# untitled.net
KiCad netlist of a schematic drawn in EAGLE
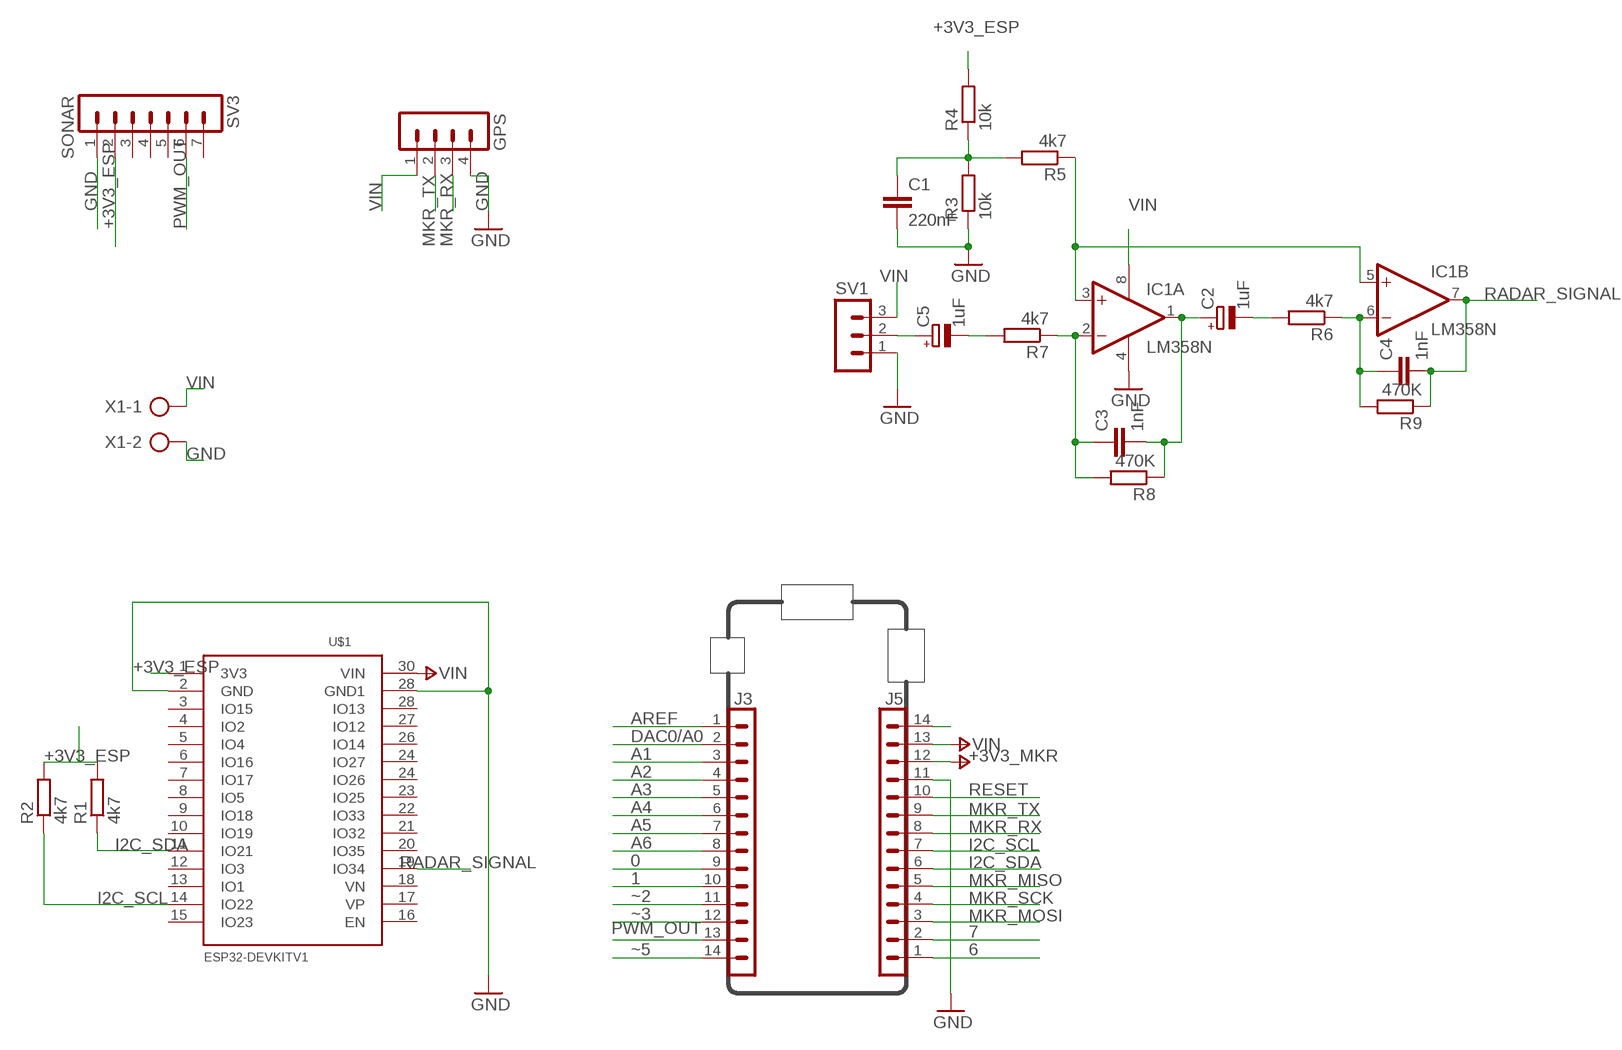
[diagram p0: schematic, sheet 1]

(export (version "E")
  (design (tool "Eeschema 10.0.6"))
  (components
    (comp (ref "C1")
      (value "220nF")
      (footprint "eagle-import:C025-025X050")
      (libsource (lib "eagle-import") (part "C-EU025-025X050"))
    )
    (comp (ref "C2")
      (value "1uF")
      (footprint "eagle-import:E2-4")
      (libsource (lib "eagle-import") (part "CPOL-EUE2-4"))
    )
    (comp (ref "C3")
      (value "1nF")
      (footprint "eagle-import:C025-025X050")
      (libsource (lib "eagle-import") (part "C-EU025-025X050"))
    )
    (comp (ref "C4")
      (value "1nF")
      (footprint "eagle-import:C025-025X050")
      (libsource (lib "eagle-import") (part "C-EU025-025X050"))
    )
    (comp (ref "C5")
      (value "1uF")
      (footprint "eagle-import:E2-4")
      (libsource (lib "eagle-import") (part "CPOL-EUE2-4"))
    )
    (comp (ref "GPS")
      (value "MA04-1")
      (footprint "eagle-import:MA04-1")
      (libsource (lib "eagle-import") (part "MA04-1"))
    )
    (comp (ref "IC1")
      (value "LM358N")
      (footprint "eagle-import:DIL08")
      (libsource (lib "eagle-import") (part "LM358N"))
    )
    (comp (ref "J3")
      (value "-")
      (footprint "eagle-import:1X14_SMD_TH")
      (fields (field (name "MANUFACTURER") "ELDECO"))
      (libsource (lib "eagle-import") (part "PINHD-1X14-SMTH-SMD-MALE/FEMALE"))
    )
    (comp (ref "J5")
      (value "-")
      (footprint "eagle-import:1X14_SMD_TH")
      (fields (field (name "MANUFACTURER") "ELDECO"))
      (libsource (lib "eagle-import") (part "PINHD-1X14-SMTH-SMD-MALE/FEMALE"))
    )
    (comp (ref "R1")
      (value "4k7")
      (footprint "eagle-import:0207_10")
      (libsource (lib "eagle-import") (part "R-EU_0207/10"))
    )
    (comp (ref "R2")
      (value "4k7")
      (footprint "eagle-import:0207_10")
      (libsource (lib "eagle-import") (part "R-EU_0207/10"))
    )
    (comp (ref "R3")
      (value "10k")
      (footprint "eagle-import:0207_10")
      (libsource (lib "eagle-import") (part "R-EU_0207/10"))
    )
    (comp (ref "R4")
      (value "10k")
      (footprint "eagle-import:0207_10")
      (libsource (lib "eagle-import") (part "R-EU_0207/10"))
    )
    (comp (ref "R5")
      (value "4k7")
      (footprint "eagle-import:0207_10")
      (libsource (lib "eagle-import") (part "R-EU_0207/10"))
    )
    (comp (ref "R6")
      (value "4k7")
      (footprint "eagle-import:0207_10")
      (libsource (lib "eagle-import") (part "R-EU_0207/10"))
    )
    (comp (ref "R7")
      (value "4k7")
      (footprint "eagle-import:0207_10")
      (libsource (lib "eagle-import") (part "R-EU_0207/10"))
    )
    (comp (ref "R8")
      (value "470K")
      (footprint "eagle-import:0207_2V")
      (libsource (lib "eagle-import") (part "R-EU_0207/2V"))
    )
    (comp (ref "R9")
      (value "470K")
      (footprint "eagle-import:0207_2V")
      (libsource (lib "eagle-import") (part "R-EU_0207/2V"))
    )
    (comp (ref "SV1")
      (value "MA03-1")
      (footprint "eagle-import:MA03-1")
      (libsource (lib "eagle-import") (part "MA03-1"))
    )
    (comp (ref "SV3")
      (value "SONAR")
      (footprint "eagle-import:MA07-1")
      (libsource (lib "eagle-import") (part "MA07-1"))
    )
    (comp (ref "U$1")
      (value "ESP32DEVKITV1")
      (footprint "eagle-import:ESP32-DEVKITV1")
      (libsource (lib "eagle-import") (part "ESP32DEVKITV1"))
    )
    (comp (ref "X1")
      (value "AK500/2-H")
      (footprint "eagle-import:AK500_2-H")
      (libsource (lib "eagle-import") (part "AK500/2-H"))
    )
  )
  (nets
    (net (code "1") (name "+3V3") (class "Default")
      (node (ref "J5") (pin "12") (pinfunction "12_12") (pintype "passive"))
    )
    (net (code "2") (name "/+3V3_ESP") (class "Default")
      (node (ref "R1") (pin "2") (pinfunction "2_2") (pintype "passive"))
      (node (ref "R2") (pin "2") (pinfunction "2_2") (pintype "passive"))
      (node (ref "R4") (pin "2") (pinfunction "2_2") (pintype "passive"))
      (node (ref "SV3") (pin "2") (pinfunction "2_2") (pintype "passive"))
      (node (ref "U$1") (pin "1") (pinfunction "3V3_1") (pintype "bidirectional"))
    )
    (net (code "3") (name "/I2C_SCL") (class "Default")
      (node (ref "J5") (pin "7") (pinfunction "7_7") (pintype "passive"))
      (node (ref "R2") (pin "1") (pinfunction "1_1") (pintype "passive"))
      (node (ref "U$1") (pin "14") (pinfunction "IO22_14") (pintype "bidirectional"))
    )
    (net (code "4") (name "/I2C_SDA") (class "Default")
      (node (ref "J5") (pin "6") (pinfunction "6_6") (pintype "passive"))
      (node (ref "R1") (pin "1") (pinfunction "1_1") (pintype "passive"))
      (node (ref "U$1") (pin "11") (pinfunction "IO21_11") (pintype "bidirectional"))
    )
    (net (code "5") (name "/MKR_MISO") (class "Default")
      (node (ref "J5") (pin "5") (pinfunction "5_5") (pintype "passive"))
    )
    (net (code "6") (name "/MKR_MOSI") (class "Default")
      (node (ref "J5") (pin "3") (pinfunction "3_3") (pintype "passive"))
    )
    (net (code "7") (name "/MKR_RX") (class "Default")
      (node (ref "GPS") (pin "3") (pinfunction "3_3") (pintype "passive"))
      (node (ref "J5") (pin "8") (pinfunction "8_8") (pintype "passive"))
    )
    (net (code "8") (name "/MKR_SCK") (class "Default")
      (node (ref "J5") (pin "4") (pinfunction "4_4") (pintype "passive"))
    )
    (net (code "9") (name "/MKR_TX") (class "Default")
      (node (ref "GPS") (pin "2") (pinfunction "2_2") (pintype "passive"))
      (node (ref "J5") (pin "9") (pinfunction "9_9") (pintype "passive"))
    )
    (net (code "10") (name "/PWM_OUT") (class "Default")
      (node (ref "J3") (pin "13") (pinfunction "13_13") (pintype "passive"))
      (node (ref "SV3") (pin "6") (pinfunction "6_6") (pintype "passive"))
    )
    (net (code "11") (name "/RADAR_SIGNAL") (class "Default")
      (node (ref "C4") (pin "2") (pinfunction "2_2") (pintype "passive"))
      (node (ref "IC1") (pin "7") (pinfunction "OUT_7") (pintype "output"))
      (node (ref "R9") (pin "1") (pinfunction "1_1") (pintype "passive"))
      (node (ref "U$1") (pin "19") (pinfunction "IO34_19") (pintype "bidirectional"))
    )
    (net (code "12") (name "GND") (class "Default")
      (node (ref "C1") (pin "2") (pinfunction "2_2") (pintype "passive"))
      (node (ref "GPS") (pin "4") (pinfunction "4_4") (pintype "passive"))
      (node (ref "IC1") (pin "4") (pinfunction "V-_4") (pintype "power_in"))
      (node (ref "J5") (pin "11") (pinfunction "11_11") (pintype "passive"))
      (node (ref "R3") (pin "1") (pinfunction "1_1") (pintype "passive"))
      (node (ref "SV1") (pin "1") (pinfunction "1_1") (pintype "passive"))
      (node (ref "SV3") (pin "1") (pinfunction "1_1") (pintype "passive"))
      (node (ref "U$1") (pin "2") (pinfunction "GND_2") (pintype "bidirectional"))
      (node (ref "U$1") (pin "28") (pinfunction "GND1_28") (pintype "bidirectional"))
      (node (ref "X1") (pin "2") (pinfunction "KL_2") (pintype "passive"))
    )
    (net (code "13") (name "Net-(C1-Pad1)") (class "Default")
      (node (ref "C1") (pin "1") (pinfunction "1_1") (pintype "passive"))
      (node (ref "R3") (pin "2") (pinfunction "2_2") (pintype "passive"))
      (node (ref "R4") (pin "1") (pinfunction "1_1") (pintype "passive"))
      (node (ref "R5") (pin "2") (pinfunction "2_2") (pintype "passive"))
    )
    (net (code "14") (name "Net-(C2-Pad-)") (class "Default")
      (node (ref "C2") (pin "-") (pinfunction "-_-") (pintype "passive"))
      (node (ref "R6") (pin "2") (pinfunction "2_2") (pintype "passive"))
    )
    (net (code "15") (name "Net-(C5-Pad+)") (class "Default")
      (node (ref "C5") (pin "+") (pinfunction "+_+") (pintype "passive"))
      (node (ref "SV1") (pin "2") (pinfunction "2_2") (pintype "passive"))
    )
    (net (code "16") (name "Net-(C5-Pad-)") (class "Default")
      (node (ref "C5") (pin "-") (pinfunction "-_-") (pintype "passive"))
      (node (ref "R7") (pin "2") (pinfunction "2_2") (pintype "passive"))
    )
    (net (code "17") (name "Net-(IC1A-+IN)") (class "Default")
      (node (ref "IC1") (pin "3") (pinfunction "+IN_3") (pintype "input"))
      (node (ref "IC1") (pin "5") (pinfunction "+IN_5") (pintype "input"))
      (node (ref "R5") (pin "1") (pinfunction "1_1") (pintype "passive"))
    )
    (net (code "18") (name "Net-(IC1A--IN)") (class "Default")
      (node (ref "C3") (pin "1") (pinfunction "1_1") (pintype "passive"))
      (node (ref "IC1") (pin "2") (pinfunction "-IN_2") (pintype "input"))
      (node (ref "R7") (pin "1") (pinfunction "1_1") (pintype "passive"))
      (node (ref "R8") (pin "2") (pinfunction "2_2") (pintype "passive"))
    )
    (net (code "19") (name "Net-(IC1A-OUT)") (class "Default")
      (node (ref "C2") (pin "+") (pinfunction "+_+") (pintype "passive"))
      (node (ref "C3") (pin "2") (pinfunction "2_2") (pintype "passive"))
      (node (ref "IC1") (pin "1") (pinfunction "OUT_1") (pintype "output"))
      (node (ref "R8") (pin "1") (pinfunction "1_1") (pintype "passive"))
    )
    (net (code "20") (name "Net-(IC1B--IN)") (class "Default")
      (node (ref "C4") (pin "1") (pinfunction "1_1") (pintype "passive"))
      (node (ref "IC1") (pin "6") (pinfunction "-IN_6") (pintype "input"))
      (node (ref "R6") (pin "1") (pinfunction "1_1") (pintype "passive"))
      (node (ref "R9") (pin "2") (pinfunction "2_2") (pintype "passive"))
    )
    (net (code "21") (name "VIN") (class "Default")
      (node (ref "GPS") (pin "1") (pinfunction "1_1") (pintype "passive"))
      (node (ref "IC1") (pin "8") (pinfunction "V+_8") (pintype "power_in"))
      (node (ref "J5") (pin "13") (pinfunction "13_13") (pintype "passive"))
      (node (ref "SV1") (pin "3") (pinfunction "3_3") (pintype "passive"))
      (node (ref "U$1") (pin "30") (pinfunction "VIN_30") (pintype "bidirectional"))
      (node (ref "X1") (pin "1") (pinfunction "KL_1") (pintype "passive"))
    )
    (net (code "22") (name "unconnected-(J3-Pad1)") (class "Default")
      (node (ref "J3") (pin "1") (pinfunction "1_1") (pintype "passive"))
    )
    (net (code "23") (name "unconnected-(J3-Pad2)") (class "Default")
      (node (ref "J3") (pin "2") (pinfunction "2_2") (pintype "passive"))
    )
    (net (code "24") (name "unconnected-(J3-Pad3)") (class "Default")
      (node (ref "J3") (pin "3") (pinfunction "3_3") (pintype "passive"))
    )
    (net (code "25") (name "unconnected-(J3-Pad4)") (class "Default")
      (node (ref "J3") (pin "4") (pinfunction "4_4") (pintype "passive"))
    )
    (net (code "26") (name "unconnected-(J3-Pad5)") (class "Default")
      (node (ref "J3") (pin "5") (pinfunction "5_5") (pintype "passive"))
    )
    (net (code "27") (name "unconnected-(J3-Pad6)") (class "Default")
      (node (ref "J3") (pin "6") (pinfunction "6_6") (pintype "passive"))
    )
    (net (code "28") (name "unconnected-(J3-Pad7)") (class "Default")
      (node (ref "J3") (pin "7") (pinfunction "7_7") (pintype "passive"))
    )
    (net (code "29") (name "unconnected-(J3-Pad8)") (class "Default")
      (node (ref "J3") (pin "8") (pinfunction "8_8") (pintype "passive"))
    )
    (net (code "30") (name "unconnected-(J3-Pad9)") (class "Default")
      (node (ref "J3") (pin "9") (pinfunction "9_9") (pintype "passive"))
    )
    (net (code "31") (name "unconnected-(J3-Pad10)") (class "Default")
      (node (ref "J3") (pin "10") (pinfunction "10_10") (pintype "passive"))
    )
    (net (code "32") (name "unconnected-(J3-Pad11)") (class "Default")
      (node (ref "J3") (pin "11") (pinfunction "11_11") (pintype "passive"))
    )
    (net (code "33") (name "unconnected-(J3-Pad12)") (class "Default")
      (node (ref "J3") (pin "12") (pinfunction "12_12") (pintype "passive"))
    )
    (net (code "34") (name "unconnected-(J3-Pad14)") (class "Default")
      (node (ref "J3") (pin "14") (pinfunction "14_14") (pintype "passive"))
    )
    (net (code "35") (name "unconnected-(J5-Pad1)") (class "Default")
      (node (ref "J5") (pin "1") (pinfunction "1_1") (pintype "passive"))
    )
    (net (code "36") (name "unconnected-(J5-Pad2)") (class "Default")
      (node (ref "J5") (pin "2") (pinfunction "2_2") (pintype "passive"))
    )
    (net (code "37") (name "unconnected-(J5-Pad10)") (class "Default")
      (node (ref "J5") (pin "10") (pinfunction "10_10") (pintype "passive"))
    )
    (net (code "38") (name "unconnected-(J5-Pad14)") (class "Default")
      (node (ref "J5") (pin "14") (pinfunction "14_14") (pintype "passive"))
    )
    (net (code "39") (name "unconnected-(SV3-Pad3)") (class "Default")
      (node (ref "SV3") (pin "3") (pinfunction "3_3") (pintype "passive"))
    )
    (net (code "40") (name "unconnected-(SV3-Pad4)") (class "Default")
      (node (ref "SV3") (pin "4") (pinfunction "4_4") (pintype "passive"))
    )
    (net (code "41") (name "unconnected-(SV3-Pad5)") (class "Default")
      (node (ref "SV3") (pin "5") (pinfunction "5_5") (pintype "passive"))
    )
    (net (code "42") (name "unconnected-(SV3-Pad7)") (class "Default")
      (node (ref "SV3") (pin "7") (pinfunction "7_7") (pintype "passive"))
    )
    (net (code "43") (name "unconnected-(U$1-EN-Pad16)") (class "Default")
      (node (ref "U$1") (pin "16") (pinfunction "EN_16") (pintype "bidirectional"))
    )
    (net (code "44") (name "unconnected-(U$1-IO1-Pad13)") (class "Default")
      (node (ref "U$1") (pin "13") (pinfunction "IO1_13") (pintype "bidirectional"))
    )
    (net (code "45") (name "unconnected-(U$1-IO2-Pad4)") (class "Default")
      (node (ref "U$1") (pin "4") (pinfunction "IO2_4") (pintype "bidirectional"))
    )
    (net (code "46") (name "unconnected-(U$1-IO3-Pad12)") (class "Default")
      (node (ref "U$1") (pin "12") (pinfunction "IO3_12") (pintype "bidirectional"))
    )
    (net (code "47") (name "unconnected-(U$1-IO4-Pad5)") (class "Default")
      (node (ref "U$1") (pin "5") (pinfunction "IO4_5") (pintype "bidirectional"))
    )
    (net (code "48") (name "unconnected-(U$1-IO5-Pad8)") (class "Default")
      (node (ref "U$1") (pin "8") (pinfunction "IO5_8") (pintype "bidirectional"))
    )
    (net (code "49") (name "unconnected-(U$1-IO12-Pad27)") (class "Default")
      (node (ref "U$1") (pin "27") (pinfunction "IO12_27") (pintype "bidirectional"))
    )
    (net (code "50") (name "unconnected-(U$1-IO13-Pad28)") (class "Default")
      (node (ref "U$1") (pin "28") (pinfunction "IO13_28") (pintype "bidirectional"))
    )
    (net (code "51") (name "unconnected-(U$1-IO14-Pad26)") (class "Default")
      (node (ref "U$1") (pin "26") (pinfunction "IO14_26") (pintype "bidirectional"))
    )
    (net (code "52") (name "unconnected-(U$1-IO15-Pad3)") (class "Default")
      (node (ref "U$1") (pin "3") (pinfunction "IO15_3") (pintype "bidirectional"))
    )
    (net (code "53") (name "unconnected-(U$1-IO16-Pad6)") (class "Default")
      (node (ref "U$1") (pin "6") (pinfunction "IO16_6") (pintype "bidirectional"))
    )
    (net (code "54") (name "unconnected-(U$1-IO17-Pad7)") (class "Default")
      (node (ref "U$1") (pin "7") (pinfunction "IO17_7") (pintype "bidirectional"))
    )
    (net (code "55") (name "unconnected-(U$1-IO18-Pad9)") (class "Default")
      (node (ref "U$1") (pin "9") (pinfunction "IO18_9") (pintype "bidirectional"))
    )
    (net (code "56") (name "unconnected-(U$1-IO19-Pad10)") (class "Default")
      (node (ref "U$1") (pin "10") (pinfunction "IO19_10") (pintype "bidirectional"))
    )
    (net (code "57") (name "unconnected-(U$1-IO23-Pad15)") (class "Default")
      (node (ref "U$1") (pin "15") (pinfunction "IO23_15") (pintype "bidirectional"))
    )
    (net (code "58") (name "unconnected-(U$1-IO25-Pad23)") (class "Default")
      (node (ref "U$1") (pin "23") (pinfunction "IO25_23") (pintype "bidirectional"))
    )
    (net (code "59") (name "unconnected-(U$1-IO26-Pad24)") (class "Default")
      (node (ref "U$1") (pin "24") (pinfunction "IO26_24") (pintype "bidirectional"))
    )
    (net (code "60") (name "unconnected-(U$1-IO27-Pad24)") (class "Default")
      (node (ref "U$1") (pin "24") (pinfunction "IO27_24") (pintype "bidirectional"))
    )
    (net (code "61") (name "unconnected-(U$1-IO32-Pad21)") (class "Default")
      (node (ref "U$1") (pin "21") (pinfunction "IO32_21") (pintype "bidirectional"))
    )
    (net (code "62") (name "unconnected-(U$1-IO33-Pad22)") (class "Default")
      (node (ref "U$1") (pin "22") (pinfunction "IO33_22") (pintype "bidirectional"))
    )
    (net (code "63") (name "unconnected-(U$1-IO35-Pad20)") (class "Default")
      (node (ref "U$1") (pin "20") (pinfunction "IO35_20") (pintype "bidirectional"))
    )
    (net (code "64") (name "unconnected-(U$1-VN-Pad18)") (class "Default")
      (node (ref "U$1") (pin "18") (pinfunction "VN_18") (pintype "bidirectional"))
    )
    (net (code "65") (name "unconnected-(U$1-VP-Pad17)") (class "Default")
      (node (ref "U$1") (pin "17") (pinfunction "VP_17") (pintype "bidirectional"))
    )
  )
)
